# CurrentAmp.net
KiCad netlist of a schematic drawn in EAGLE
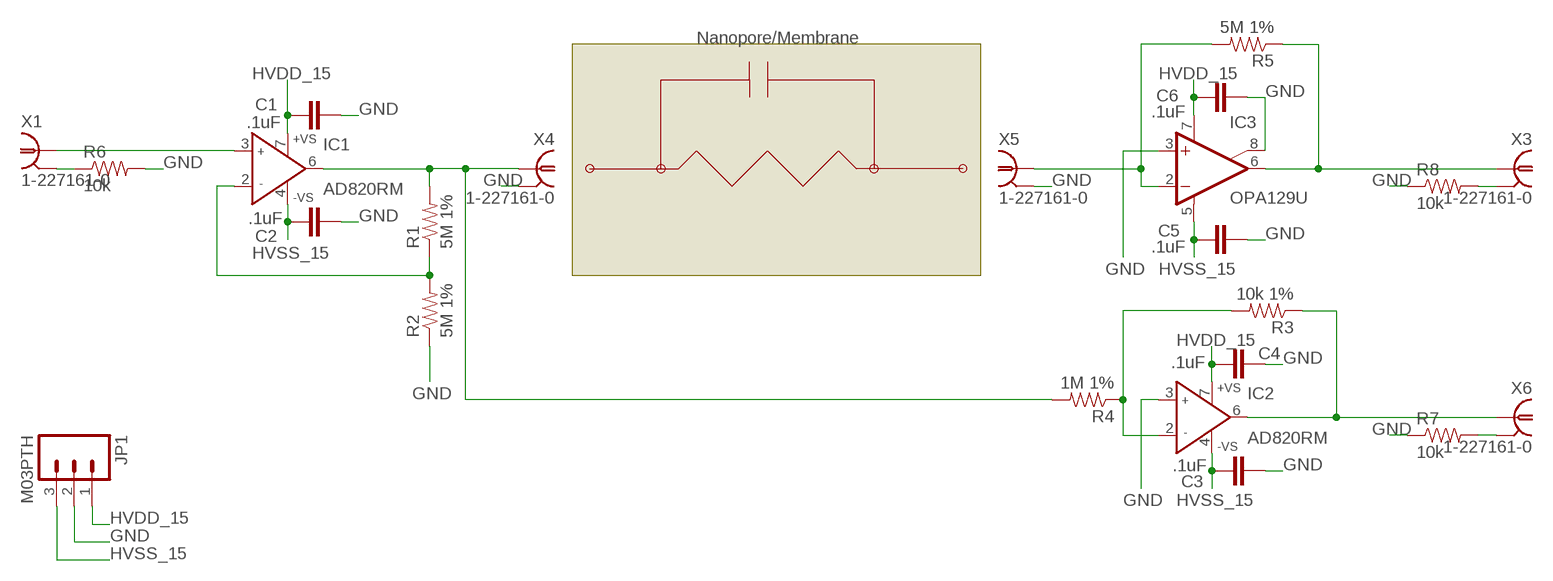
[diagram p0: schematic, sheet 1]

(export (version "E")
  (design (tool "Eeschema 10.0.6"))
  (components
    (comp (ref "C1")
      (value ".1uF")
      (footprint "eagle-import:0805")
      (libsource (lib "eagle-import") (part "CAP0805"))
    )
    (comp (ref "C2")
      (value ".1uF")
      (footprint "eagle-import:0805")
      (libsource (lib "eagle-import") (part "CAP0805"))
    )
    (comp (ref "C3")
      (value ".1uF")
      (footprint "eagle-import:0805")
      (libsource (lib "eagle-import") (part "CAP0805"))
    )
    (comp (ref "C4")
      (value ".1uF")
      (footprint "eagle-import:0805")
      (libsource (lib "eagle-import") (part "CAP0805"))
    )
    (comp (ref "C5")
      (value ".1uF")
      (footprint "eagle-import:0805")
      (libsource (lib "eagle-import") (part "CAP0805"))
    )
    (comp (ref "C6")
      (value ".1uF")
      (footprint "eagle-import:0805")
      (libsource (lib "eagle-import") (part "CAP0805"))
    )
    (comp (ref "IC1")
      (value "AD820RM")
      (footprint "eagle-import:MSOP08")
      (fields (field (name "MF") "ALTERA CORPORATION") (field (name "MPN") "AD820ARZ"))
      (libsource (lib "eagle-import") (part "AD820RM"))
    )
    (comp (ref "IC2")
      (value "AD820RM")
      (footprint "eagle-import:MSOP08")
      (fields (field (name "MF") "ALTERA CORPORATION") (field (name "MPN") "AD820ARZ"))
      (libsource (lib "eagle-import") (part "AD820RM"))
    )
    (comp (ref "IC3")
      (value "OPA129U")
      (footprint "eagle-import:SO08")
      (fields (field (name "MF") "TEXAS INSTRUMENTS"))
      (libsource (lib "eagle-import") (part "OPA129U"))
    )
    (comp (ref "JP1")
      (value "M03PTH")
      (footprint "eagle-import:1X03")
      (libsource (lib "eagle-import") (part "M03PTH"))
    )
    (comp (ref "R1")
      (value "5M 1%")
      (footprint "eagle-import:0805")
      (libsource (lib "eagle-import") (part "RESISTOR0805-RES"))
    )
    (comp (ref "R2")
      (value "5M 1%")
      (footprint "eagle-import:0805")
      (libsource (lib "eagle-import") (part "RESISTOR0805-RES"))
    )
    (comp (ref "R3")
      (value "10k 1%")
      (footprint "eagle-import:0805")
      (libsource (lib "eagle-import") (part "RESISTOR0805-RES"))
    )
    (comp (ref "R4")
      (value "1M 1%")
      (footprint "eagle-import:0805")
      (libsource (lib "eagle-import") (part "RESISTOR0805-RES"))
    )
    (comp (ref "R5")
      (value "5M 1%")
      (footprint "eagle-import:0805")
      (libsource (lib "eagle-import") (part "RESISTOR0805-RES"))
    )
    (comp (ref "R6")
      (value "10k")
      (footprint "eagle-import:0805")
      (libsource (lib "eagle-import") (part "RESISTOR0805-RES"))
    )
    (comp (ref "R7")
      (value "10k")
      (footprint "eagle-import:0805")
      (libsource (lib "eagle-import") (part "RESISTOR0805-RES"))
    )
    (comp (ref "R8")
      (value "10k")
      (footprint "eagle-import:0805")
      (libsource (lib "eagle-import") (part "RESISTOR0805-RES"))
    )
    (comp (ref "X1")
      (value "1-227161-0")
      (footprint "eagle-import:AMP_227161")
      (fields (field (name "MF") "TYCO ELECTRONICS") (field (name "MPN") "1-227161"))
      (libsource (lib "eagle-import") (part "?2271611--0"))
    )
    (comp (ref "X3")
      (value "1-227161-0")
      (footprint "eagle-import:AMP_227161")
      (fields (field (name "MF") "TYCO ELECTRONICS") (field (name "MPN") "1-227161"))
      (libsource (lib "eagle-import") (part "?2271611--0"))
    )
    (comp (ref "X4")
      (value "1-227161-0")
      (footprint "eagle-import:AMP_227161")
      (fields (field (name "MF") "TYCO ELECTRONICS") (field (name "MPN") "1-227161"))
      (libsource (lib "eagle-import") (part "?2271611--0"))
    )
    (comp (ref "X5")
      (value "1-227161-0")
      (footprint "eagle-import:AMP_227161")
      (fields (field (name "MF") "TYCO ELECTRONICS") (field (name "MPN") "1-227161"))
      (libsource (lib "eagle-import") (part "?2271611--0"))
    )
    (comp (ref "X6")
      (value "1-227161-0")
      (footprint "eagle-import:AMP_227161")
      (fields (field (name "MF") "TYCO ELECTRONICS") (field (name "MPN") "1-227161"))
      (libsource (lib "eagle-import") (part "?2271611--0"))
    )
  )
  (nets
    (net (code "1") (name "/GND") (class "Default")
      (node (ref "C1") (pin "2") (pinfunction "2_2") (pintype "passive"))
      (node (ref "C2") (pin "2") (pinfunction "2_2") (pintype "passive"))
      (node (ref "C3") (pin "2") (pinfunction "2_2") (pintype "passive"))
      (node (ref "C4") (pin "2") (pinfunction "2_2") (pintype "passive"))
      (node (ref "C5") (pin "2") (pinfunction "2_2") (pintype "passive"))
      (node (ref "C6") (pin "2") (pinfunction "2_2") (pintype "passive"))
      (node (ref "IC2") (pin "3") (pinfunction "IN+_3") (pintype "input"))
      (node (ref "IC3") (pin "3") (pinfunction "+IN_3") (pintype "input"))
      (node (ref "IC3") (pin "8") (pinfunction "SUBS_8") (pintype "passive"))
      (node (ref "JP1") (pin "2") (pinfunction "2_2") (pintype "passive"))
      (node (ref "R2") (pin "1") (pinfunction "1_1") (pintype "passive"))
      (node (ref "R6") (pin "2") (pinfunction "2_2") (pintype "passive"))
      (node (ref "R7") (pin "1") (pinfunction "1_1") (pintype "passive"))
      (node (ref "R8") (pin "1") (pinfunction "1_1") (pintype "passive"))
      (node (ref "X4") (pin "2") (pinfunction "2_2") (pintype "passive"))
      (node (ref "X5") (pin "2") (pinfunction "2_2") (pintype "passive"))
    )
    (net (code "2") (name "/HVDD_15") (class "Default")
      (node (ref "C1") (pin "1") (pinfunction "1_1") (pintype "passive"))
      (node (ref "C4") (pin "1") (pinfunction "1_1") (pintype "passive"))
      (node (ref "C6") (pin "1") (pinfunction "1_1") (pintype "passive"))
      (node (ref "IC1") (pin "7") (pinfunction "+VS_7") (pintype "input"))
      (node (ref "IC2") (pin "7") (pinfunction "+VS_7") (pintype "input"))
      (node (ref "IC3") (pin "7") (pinfunction "V+_7") (pintype "power_in"))
      (node (ref "JP1") (pin "1") (pinfunction "1_1") (pintype "passive"))
    )
    (net (code "3") (name "/HVSS_15") (class "Default")
      (node (ref "C2") (pin "1") (pinfunction "1_1") (pintype "passive"))
      (node (ref "C3") (pin "1") (pinfunction "1_1") (pintype "passive"))
      (node (ref "C5") (pin "1") (pinfunction "1_1") (pintype "passive"))
      (node (ref "IC1") (pin "4") (pinfunction "-VS_4") (pintype "input"))
      (node (ref "IC2") (pin "4") (pinfunction "-VS_4") (pintype "input"))
      (node (ref "IC3") (pin "5") (pinfunction "V-_5") (pintype "power_in"))
      (node (ref "JP1") (pin "3") (pinfunction "3_3") (pintype "passive"))
    )
    (net (code "4") (name "Net-(IC1-IN+)") (class "Default")
      (node (ref "IC1") (pin "3") (pinfunction "IN+_3") (pintype "input"))
      (node (ref "X1") (pin "1") (pinfunction "1_1") (pintype "passive"))
    )
    (net (code "5") (name "Net-(IC1-IN-)") (class "Default")
      (node (ref "IC1") (pin "2") (pinfunction "IN-_2") (pintype "input"))
      (node (ref "R1") (pin "1") (pinfunction "1_1") (pintype "passive"))
      (node (ref "R2") (pin "2") (pinfunction "2_2") (pintype "passive"))
    )
    (net (code "6") (name "Net-(IC1-OUT)") (class "Default")
      (node (ref "IC1") (pin "6") (pinfunction "OUT_6") (pintype "output"))
      (node (ref "R1") (pin "2") (pinfunction "2_2") (pintype "passive"))
      (node (ref "R4") (pin "2") (pinfunction "2_2") (pintype "passive"))
      (node (ref "X4") (pin "1") (pinfunction "1_1") (pintype "passive"))
    )
    (net (code "7") (name "Net-(IC2-IN-)") (class "Default")
      (node (ref "IC2") (pin "2") (pinfunction "IN-_2") (pintype "input"))
      (node (ref "R3") (pin "2") (pinfunction "2_2") (pintype "passive"))
      (node (ref "R4") (pin "1") (pinfunction "1_1") (pintype "passive"))
    )
    (net (code "8") (name "Net-(IC2-OUT)") (class "Default")
      (node (ref "IC2") (pin "6") (pinfunction "OUT_6") (pintype "output"))
      (node (ref "R3") (pin "1") (pinfunction "1_1") (pintype "passive"))
      (node (ref "X6") (pin "1") (pinfunction "1_1") (pintype "passive"))
    )
    (net (code "9") (name "Net-(IC3--IN)") (class "Default")
      (node (ref "IC3") (pin "2") (pinfunction "-IN_2") (pintype "input"))
      (node (ref "R5") (pin "2") (pinfunction "2_2") (pintype "passive"))
      (node (ref "X5") (pin "1") (pinfunction "1_1") (pintype "passive"))
    )
    (net (code "10") (name "Net-(IC3-OUT)") (class "Default")
      (node (ref "IC3") (pin "6") (pinfunction "OUT_6") (pintype "output"))
      (node (ref "R5") (pin "1") (pinfunction "1_1") (pintype "passive"))
      (node (ref "X3") (pin "1") (pinfunction "1_1") (pintype "passive"))
    )
    (net (code "11") (name "Net-(R6-Pad1)") (class "Default")
      (node (ref "R6") (pin "1") (pinfunction "1_1") (pintype "passive"))
      (node (ref "X1") (pin "2") (pinfunction "2_2") (pintype "passive"))
    )
    (net (code "12") (name "Net-(R7-Pad2)") (class "Default")
      (node (ref "R7") (pin "2") (pinfunction "2_2") (pintype "passive"))
      (node (ref "X6") (pin "2") (pinfunction "2_2") (pintype "passive"))
    )
    (net (code "13") (name "Net-(R8-Pad2)") (class "Default")
      (node (ref "R8") (pin "2") (pinfunction "2_2") (pintype "passive"))
      (node (ref "X3") (pin "2") (pinfunction "2_2") (pintype "passive"))
    )
  )
)
